# Stepper_2_0.net
KiCad netlist of a schematic drawn in EAGLE
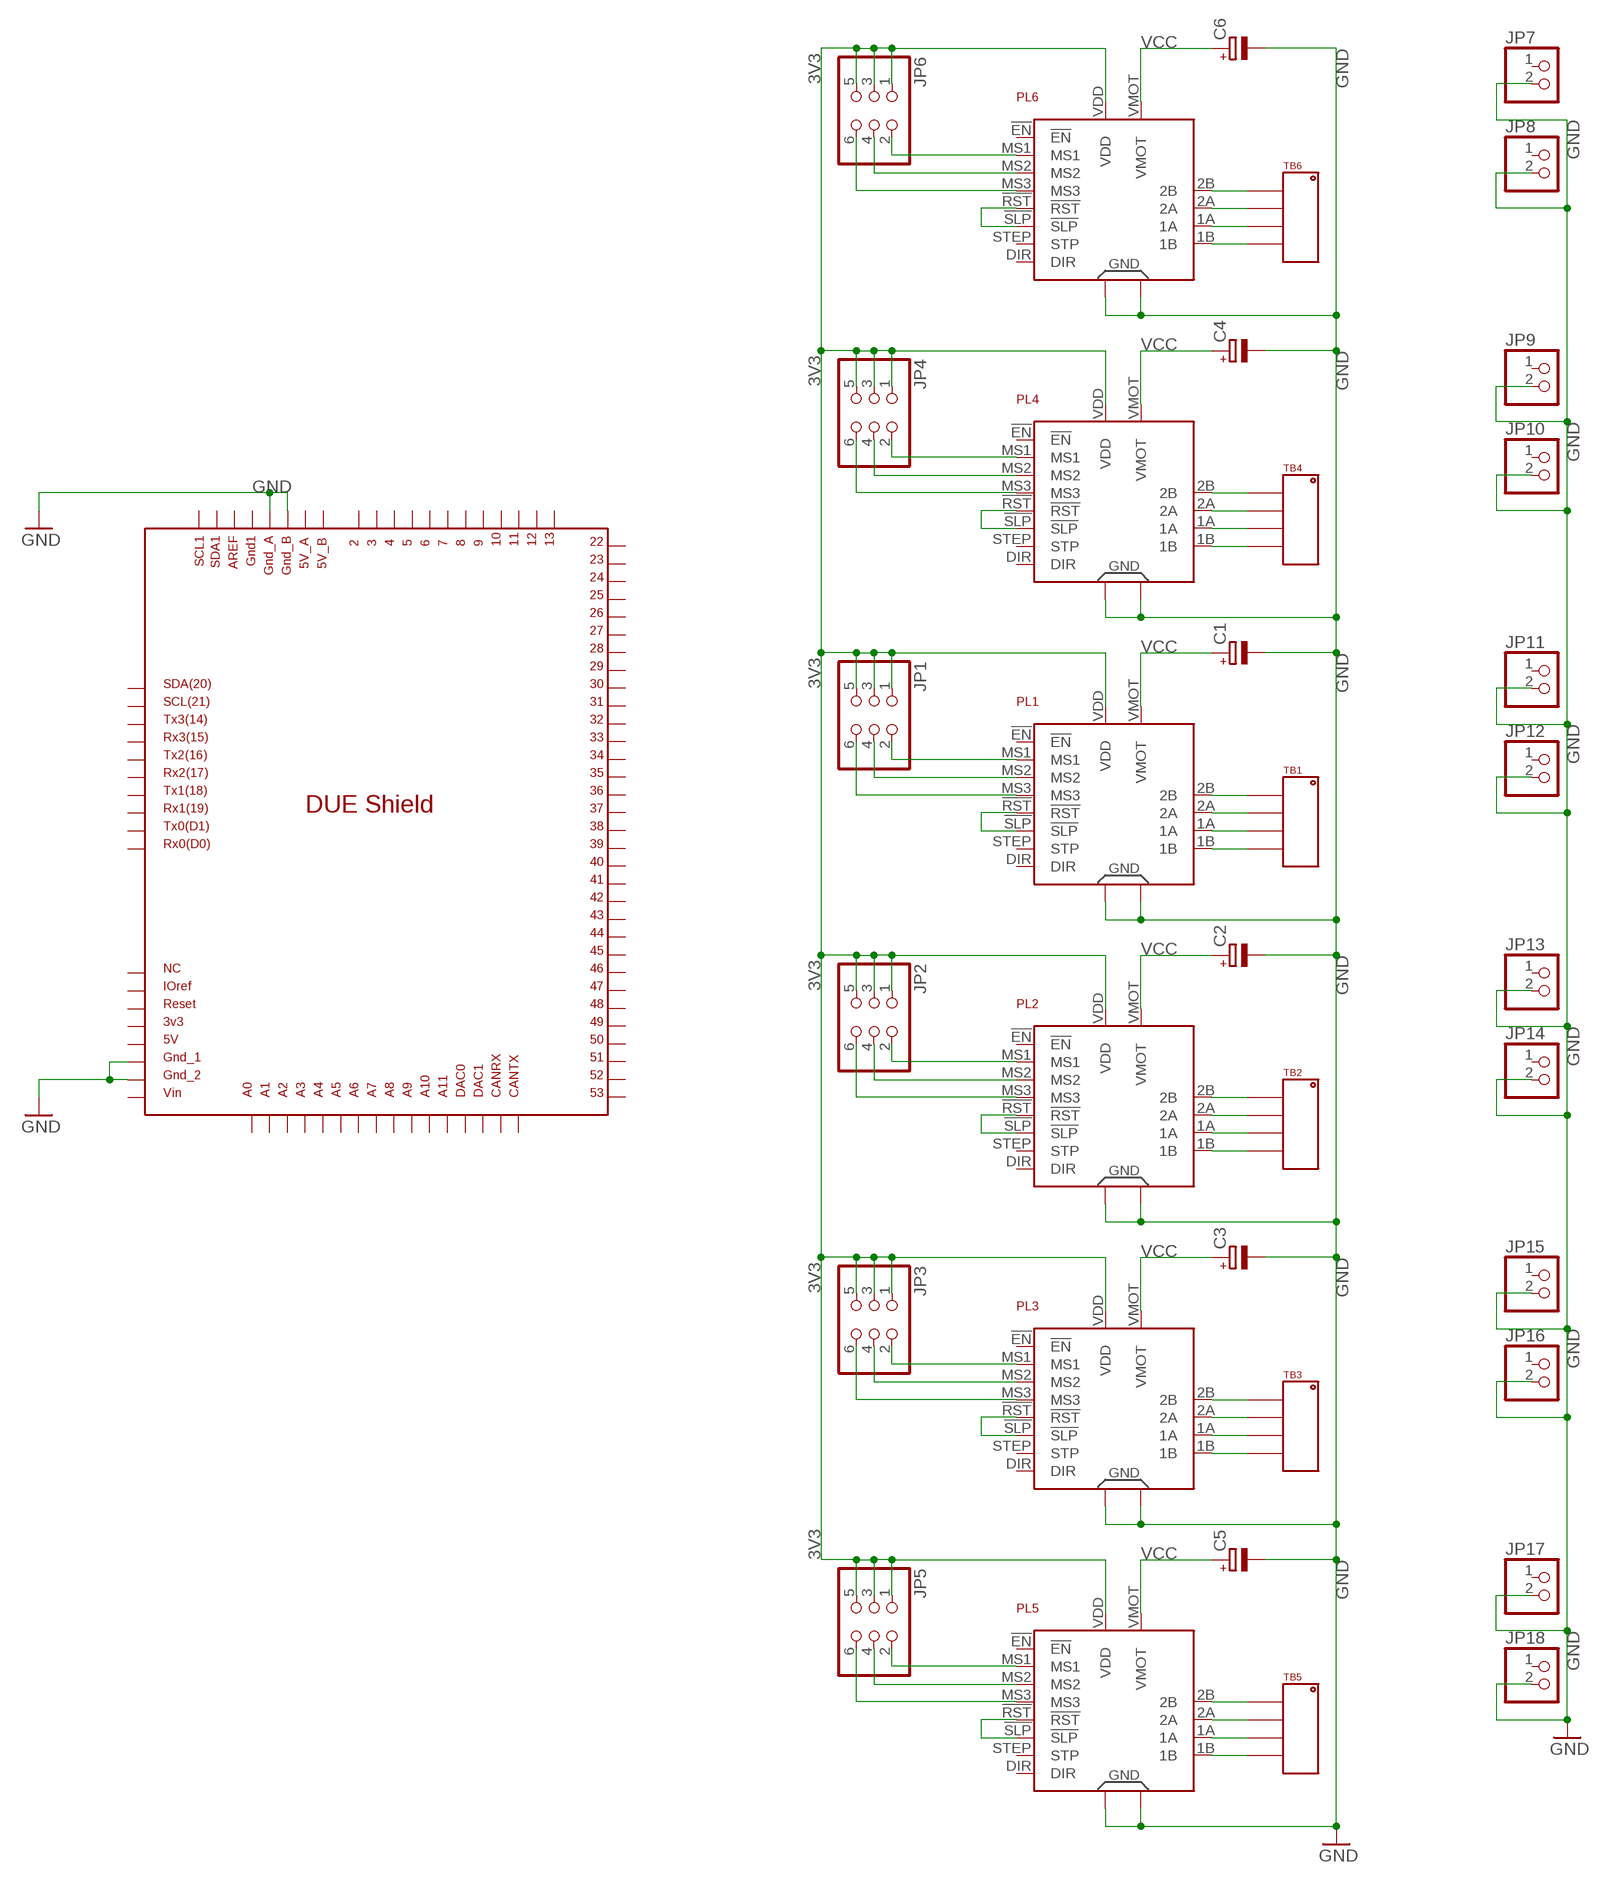
[diagram p0: schematic, sheet 1]

(export (version "E")
  (design (tool "Eeschema 10.0.6"))
  (components
    (comp (ref "C1")
      (value "CPOL-EUETR2")
      (footprint "eagle-import:ETR2")
      (libsource (lib "eagle-import") (part "CPOL-EUETR2"))
    )
    (comp (ref "C2")
      (value "CPOL-EUETR2")
      (footprint "eagle-import:ETR2")
      (libsource (lib "eagle-import") (part "CPOL-EUETR2"))
    )
    (comp (ref "C3")
      (value "CPOL-EUETR2")
      (footprint "eagle-import:ETR2")
      (libsource (lib "eagle-import") (part "CPOL-EUETR2"))
    )
    (comp (ref "C4")
      (value "CPOL-EUETR2")
      (footprint "eagle-import:ETR2")
      (libsource (lib "eagle-import") (part "CPOL-EUETR2"))
    )
    (comp (ref "C5")
      (value "CPOL-EUETR2")
      (footprint "eagle-import:ETR2")
      (libsource (lib "eagle-import") (part "CPOL-EUETR2"))
    )
    (comp (ref "C6")
      (value "CPOL-EUETR2")
      (footprint "eagle-import:ETR2")
      (libsource (lib "eagle-import") (part "CPOL-EUETR2"))
    )
    (comp (ref "JP1")
      (value "PINHD-2X3")
      (footprint "eagle-import:2X03")
      (libsource (lib "eagle-import") (part "PINHD-2X3"))
    )
    (comp (ref "JP2")
      (value "PINHD-2X3")
      (footprint "eagle-import:2X03")
      (libsource (lib "eagle-import") (part "PINHD-2X3"))
    )
    (comp (ref "JP3")
      (value "PINHD-2X3")
      (footprint "eagle-import:2X03")
      (libsource (lib "eagle-import") (part "PINHD-2X3"))
    )
    (comp (ref "JP4")
      (value "PINHD-2X3")
      (footprint "eagle-import:2X03")
      (libsource (lib "eagle-import") (part "PINHD-2X3"))
    )
    (comp (ref "JP5")
      (value "PINHD-2X3")
      (footprint "eagle-import:2X03")
      (libsource (lib "eagle-import") (part "PINHD-2X3"))
    )
    (comp (ref "JP6")
      (value "PINHD-2X3")
      (footprint "eagle-import:2X03")
      (libsource (lib "eagle-import") (part "PINHD-2X3"))
    )
    (comp (ref "JP7")
      (value "PINHD-1X2")
      (footprint "eagle-import:1X02")
      (libsource (lib "eagle-import") (part "PINHD-1X2"))
    )
    (comp (ref "JP8")
      (value "PINHD-1X2")
      (footprint "eagle-import:1X02")
      (libsource (lib "eagle-import") (part "PINHD-1X2"))
    )
    (comp (ref "JP9")
      (value "PINHD-1X2")
      (footprint "eagle-import:1X02")
      (libsource (lib "eagle-import") (part "PINHD-1X2"))
    )
    (comp (ref "JP10")
      (value "PINHD-1X2")
      (footprint "eagle-import:1X02")
      (libsource (lib "eagle-import") (part "PINHD-1X2"))
    )
    (comp (ref "JP11")
      (value "PINHD-1X2")
      (footprint "eagle-import:1X02")
      (libsource (lib "eagle-import") (part "PINHD-1X2"))
    )
    (comp (ref "JP12")
      (value "PINHD-1X2")
      (footprint "eagle-import:1X02")
      (libsource (lib "eagle-import") (part "PINHD-1X2"))
    )
    (comp (ref "JP13")
      (value "PINHD-1X2")
      (footprint "eagle-import:1X02")
      (libsource (lib "eagle-import") (part "PINHD-1X2"))
    )
    (comp (ref "JP14")
      (value "PINHD-1X2")
      (footprint "eagle-import:1X02")
      (libsource (lib "eagle-import") (part "PINHD-1X2"))
    )
    (comp (ref "JP15")
      (value "PINHD-1X2")
      (footprint "eagle-import:1X02")
      (libsource (lib "eagle-import") (part "PINHD-1X2"))
    )
    (comp (ref "JP16")
      (value "PINHD-1X2")
      (footprint "eagle-import:1X02")
      (libsource (lib "eagle-import") (part "PINHD-1X2"))
    )
    (comp (ref "JP17")
      (value "PINHD-1X2")
      (footprint "eagle-import:1X02")
      (libsource (lib "eagle-import") (part "PINHD-1X2"))
    )
    (comp (ref "JP18")
      (value "PINHD-1X2")
      (footprint "eagle-import:1X02")
      (libsource (lib "eagle-import") (part "PINHD-1X2"))
    )
    (comp (ref "PL1")
      (value "A4988X")
      (footprint "eagle-import:MD09X")
      (libsource (lib "eagle-import") (part "A4988X"))
    )
    (comp (ref "PL2")
      (value "A4988X")
      (footprint "eagle-import:MD09X")
      (libsource (lib "eagle-import") (part "A4988X"))
    )
    (comp (ref "PL3")
      (value "A4988X")
      (footprint "eagle-import:MD09X")
      (libsource (lib "eagle-import") (part "A4988X"))
    )
    (comp (ref "PL4")
      (value "A4988X")
      (footprint "eagle-import:MD09X")
      (libsource (lib "eagle-import") (part "A4988X"))
    )
    (comp (ref "PL5")
      (value "A4988X")
      (footprint "eagle-import:MD09X")
      (libsource (lib "eagle-import") (part "A4988X"))
    )
    (comp (ref "PL6")
      (value "A4988X")
      (footprint "eagle-import:MD09X")
      (libsource (lib "eagle-import") (part "A4988X"))
    )
    (comp (ref "TB1")
      (value "TB_HEAD_3.5MM_01X04")
      (footprint "eagle-import:TB_HEAD_3.5MM_01X04")
      (libsource (lib "eagle-import") (part "TB_HEAD_3.5MM_01X04"))
    )
    (comp (ref "TB2")
      (value "TB_HEAD_3.5MM_01X04")
      (footprint "eagle-import:TB_HEAD_3.5MM_01X04")
      (libsource (lib "eagle-import") (part "TB_HEAD_3.5MM_01X04"))
    )
    (comp (ref "TB3")
      (value "TB_HEAD_3.5MM_01X04")
      (footprint "eagle-import:TB_HEAD_3.5MM_01X04")
      (libsource (lib "eagle-import") (part "TB_HEAD_3.5MM_01X04"))
    )
    (comp (ref "TB4")
      (value "TB_HEAD_3.5MM_01X04")
      (footprint "eagle-import:TB_HEAD_3.5MM_01X04")
      (libsource (lib "eagle-import") (part "TB_HEAD_3.5MM_01X04"))
    )
    (comp (ref "TB5")
      (value "TB_HEAD_3.5MM_01X04")
      (footprint "eagle-import:TB_HEAD_3.5MM_01X04")
      (libsource (lib "eagle-import") (part "TB_HEAD_3.5MM_01X04"))
    )
    (comp (ref "TB6")
      (value "TB_HEAD_3.5MM_01X04")
      (footprint "eagle-import:TB_HEAD_3.5MM_01X04")
      (libsource (lib "eagle-import") (part "TB_HEAD_3.5MM_01X04"))
    )
    (comp (ref "U$1")
      (value "DUE(NOSPI)")
      (footprint "eagle-import:DUE(NOSPI)")
      (libsource (lib "eagle-import") (part "DUE(NOSPI)"))
    )
  )
  (nets
    (net (code "1") (name "/3V3") (class "Default")
      (node (ref "JP1") (pin "1") (pinfunction "1_1") (pintype "passive"))
      (node (ref "JP1") (pin "3") (pinfunction "3_3") (pintype "passive"))
      (node (ref "JP1") (pin "5") (pinfunction "5_5") (pintype "passive"))
      (node (ref "JP2") (pin "1") (pinfunction "1_1") (pintype "passive"))
      (node (ref "JP2") (pin "3") (pinfunction "3_3") (pintype "passive"))
      (node (ref "JP2") (pin "5") (pinfunction "5_5") (pintype "passive"))
      (node (ref "JP3") (pin "1") (pinfunction "1_1") (pintype "passive"))
      (node (ref "JP3") (pin "3") (pinfunction "3_3") (pintype "passive"))
      (node (ref "JP3") (pin "5") (pinfunction "5_5") (pintype "passive"))
      (node (ref "JP4") (pin "1") (pinfunction "1_1") (pintype "passive"))
      (node (ref "JP4") (pin "3") (pinfunction "3_3") (pintype "passive"))
      (node (ref "JP4") (pin "5") (pinfunction "5_5") (pintype "passive"))
      (node (ref "JP5") (pin "1") (pinfunction "1_1") (pintype "passive"))
      (node (ref "JP5") (pin "3") (pinfunction "3_3") (pintype "passive"))
      (node (ref "JP5") (pin "5") (pinfunction "5_5") (pintype "passive"))
      (node (ref "JP6") (pin "1") (pinfunction "1_1") (pintype "passive"))
      (node (ref "JP6") (pin "3") (pinfunction "3_3") (pintype "passive"))
      (node (ref "JP6") (pin "5") (pinfunction "5_5") (pintype "passive"))
      (node (ref "PL1") (pin "VDD") (pinfunction "VDD_VDD") (pintype "bidirectional"))
      (node (ref "PL2") (pin "VDD") (pinfunction "VDD_VDD") (pintype "bidirectional"))
      (node (ref "PL3") (pin "VDD") (pinfunction "VDD_VDD") (pintype "bidirectional"))
      (node (ref "PL4") (pin "VDD") (pinfunction "VDD_VDD") (pintype "bidirectional"))
      (node (ref "PL5") (pin "VDD") (pinfunction "VDD_VDD") (pintype "bidirectional"))
      (node (ref "PL6") (pin "VDD") (pinfunction "VDD_VDD") (pintype "bidirectional"))
    )
    (net (code "2") (name "/VCC") (class "Default")
      (node (ref "C1") (pin "+") (pinfunction "+_+") (pintype "passive"))
      (node (ref "C2") (pin "+") (pinfunction "+_+") (pintype "passive"))
      (node (ref "C3") (pin "+") (pinfunction "+_+") (pintype "passive"))
      (node (ref "C4") (pin "+") (pinfunction "+_+") (pintype "passive"))
      (node (ref "C5") (pin "+") (pinfunction "+_+") (pintype "passive"))
      (node (ref "C6") (pin "+") (pinfunction "+_+") (pintype "passive"))
      (node (ref "PL1") (pin "VMOT") (pinfunction "VMOT_VMOT") (pintype "bidirectional"))
      (node (ref "PL2") (pin "VMOT") (pinfunction "VMOT_VMOT") (pintype "bidirectional"))
      (node (ref "PL3") (pin "VMOT") (pinfunction "VMOT_VMOT") (pintype "bidirectional"))
      (node (ref "PL4") (pin "VMOT") (pinfunction "VMOT_VMOT") (pintype "bidirectional"))
      (node (ref "PL5") (pin "VMOT") (pinfunction "VMOT_VMOT") (pintype "bidirectional"))
      (node (ref "PL6") (pin "VMOT") (pinfunction "VMOT_VMOT") (pintype "bidirectional"))
    )
    (net (code "3") (name "GND") (class "Default")
      (node (ref "C1") (pin "-") (pinfunction "-_-") (pintype "passive"))
      (node (ref "C2") (pin "-") (pinfunction "-_-") (pintype "passive"))
      (node (ref "C3") (pin "-") (pinfunction "-_-") (pintype "passive"))
      (node (ref "C4") (pin "-") (pinfunction "-_-") (pintype "passive"))
      (node (ref "C5") (pin "-") (pinfunction "-_-") (pintype "passive"))
      (node (ref "C6") (pin "-") (pinfunction "-_-") (pintype "passive"))
      (node (ref "JP10") (pin "2") (pinfunction "2_2") (pintype "passive"))
      (node (ref "JP11") (pin "2") (pinfunction "2_2") (pintype "passive"))
      (node (ref "JP12") (pin "2") (pinfunction "2_2") (pintype "passive"))
      (node (ref "JP13") (pin "2") (pinfunction "2_2") (pintype "passive"))
      (node (ref "JP14") (pin "2") (pinfunction "2_2") (pintype "passive"))
      (node (ref "JP15") (pin "2") (pinfunction "2_2") (pintype "passive"))
      (node (ref "JP16") (pin "2") (pinfunction "2_2") (pintype "passive"))
      (node (ref "JP17") (pin "2") (pinfunction "2_2") (pintype "passive"))
      (node (ref "JP18") (pin "2") (pinfunction "2_2") (pintype "passive"))
      (node (ref "JP7") (pin "2") (pinfunction "2_2") (pintype "passive"))
      (node (ref "JP8") (pin "2") (pinfunction "2_2") (pintype "passive"))
      (node (ref "JP9") (pin "2") (pinfunction "2_2") (pintype "passive"))
      (node (ref "PL1") (pin "GND1") (pinfunction "GND1_GND1") (pintype "bidirectional"))
      (node (ref "PL1") (pin "GND2") (pinfunction "GND2_GND2") (pintype "bidirectional"))
      (node (ref "PL2") (pin "GND1") (pinfunction "GND1_GND1") (pintype "bidirectional"))
      (node (ref "PL2") (pin "GND2") (pinfunction "GND2_GND2") (pintype "bidirectional"))
      (node (ref "PL3") (pin "GND1") (pinfunction "GND1_GND1") (pintype "bidirectional"))
      (node (ref "PL3") (pin "GND2") (pinfunction "GND2_GND2") (pintype "bidirectional"))
      (node (ref "PL4") (pin "GND1") (pinfunction "GND1_GND1") (pintype "bidirectional"))
      (node (ref "PL4") (pin "GND2") (pinfunction "GND2_GND2") (pintype "bidirectional"))
      (node (ref "PL5") (pin "GND1") (pinfunction "GND1_GND1") (pintype "bidirectional"))
      (node (ref "PL5") (pin "GND2") (pinfunction "GND2_GND2") (pintype "bidirectional"))
      (node (ref "PL6") (pin "GND1") (pinfunction "GND1_GND1") (pintype "bidirectional"))
      (node (ref "PL6") (pin "GND2") (pinfunction "GND2_GND2") (pintype "bidirectional"))
      (node (ref "U$1") (pin "GND_1") (pinfunction "GND_1_GND_1") (pintype "bidirectional"))
      (node (ref "U$1") (pin "GND_2") (pinfunction "GND_2_GND_2") (pintype "bidirectional"))
      (node (ref "U$1") (pin "GND_A") (pinfunction "GND_A_GND_A") (pintype "bidirectional"))
      (node (ref "U$1") (pin "GND_B") (pinfunction "GND_B_GND_B") (pintype "bidirectional"))
    )
    (net (code "4") (name "Net-(JP1-Pad2)") (class "Default")
      (node (ref "JP1") (pin "2") (pinfunction "2_2") (pintype "passive"))
      (node (ref "PL1") (pin "MS1") (pinfunction "MS1_MS1") (pintype "bidirectional"))
    )
    (net (code "5") (name "Net-(JP1-Pad4)") (class "Default")
      (node (ref "JP1") (pin "4") (pinfunction "4_4") (pintype "passive"))
      (node (ref "PL1") (pin "MS2") (pinfunction "MS2_MS2") (pintype "bidirectional"))
    )
    (net (code "6") (name "Net-(JP1-Pad6)") (class "Default")
      (node (ref "JP1") (pin "6") (pinfunction "6_6") (pintype "passive"))
      (node (ref "PL1") (pin "MS3") (pinfunction "MS3_MS3") (pintype "bidirectional"))
    )
    (net (code "7") (name "Net-(JP2-Pad2)") (class "Default")
      (node (ref "JP2") (pin "2") (pinfunction "2_2") (pintype "passive"))
      (node (ref "PL2") (pin "MS1") (pinfunction "MS1_MS1") (pintype "bidirectional"))
    )
    (net (code "8") (name "Net-(JP2-Pad4)") (class "Default")
      (node (ref "JP2") (pin "4") (pinfunction "4_4") (pintype "passive"))
      (node (ref "PL2") (pin "MS2") (pinfunction "MS2_MS2") (pintype "bidirectional"))
    )
    (net (code "9") (name "Net-(JP2-Pad6)") (class "Default")
      (node (ref "JP2") (pin "6") (pinfunction "6_6") (pintype "passive"))
      (node (ref "PL2") (pin "MS3") (pinfunction "MS3_MS3") (pintype "bidirectional"))
    )
    (net (code "10") (name "Net-(JP3-Pad2)") (class "Default")
      (node (ref "JP3") (pin "2") (pinfunction "2_2") (pintype "passive"))
      (node (ref "PL3") (pin "MS1") (pinfunction "MS1_MS1") (pintype "bidirectional"))
    )
    (net (code "11") (name "Net-(JP3-Pad4)") (class "Default")
      (node (ref "JP3") (pin "4") (pinfunction "4_4") (pintype "passive"))
      (node (ref "PL3") (pin "MS2") (pinfunction "MS2_MS2") (pintype "bidirectional"))
    )
    (net (code "12") (name "Net-(JP3-Pad6)") (class "Default")
      (node (ref "JP3") (pin "6") (pinfunction "6_6") (pintype "passive"))
      (node (ref "PL3") (pin "MS3") (pinfunction "MS3_MS3") (pintype "bidirectional"))
    )
    (net (code "13") (name "Net-(JP4-Pad2)") (class "Default")
      (node (ref "JP4") (pin "2") (pinfunction "2_2") (pintype "passive"))
      (node (ref "PL4") (pin "MS1") (pinfunction "MS1_MS1") (pintype "bidirectional"))
    )
    (net (code "14") (name "Net-(JP4-Pad4)") (class "Default")
      (node (ref "JP4") (pin "4") (pinfunction "4_4") (pintype "passive"))
      (node (ref "PL4") (pin "MS2") (pinfunction "MS2_MS2") (pintype "bidirectional"))
    )
    (net (code "15") (name "Net-(JP4-Pad6)") (class "Default")
      (node (ref "JP4") (pin "6") (pinfunction "6_6") (pintype "passive"))
      (node (ref "PL4") (pin "MS3") (pinfunction "MS3_MS3") (pintype "bidirectional"))
    )
    (net (code "16") (name "Net-(JP5-Pad2)") (class "Default")
      (node (ref "JP5") (pin "2") (pinfunction "2_2") (pintype "passive"))
      (node (ref "PL5") (pin "MS1") (pinfunction "MS1_MS1") (pintype "bidirectional"))
    )
    (net (code "17") (name "Net-(JP5-Pad4)") (class "Default")
      (node (ref "JP5") (pin "4") (pinfunction "4_4") (pintype "passive"))
      (node (ref "PL5") (pin "MS2") (pinfunction "MS2_MS2") (pintype "bidirectional"))
    )
    (net (code "18") (name "Net-(JP5-Pad6)") (class "Default")
      (node (ref "JP5") (pin "6") (pinfunction "6_6") (pintype "passive"))
      (node (ref "PL5") (pin "MS3") (pinfunction "MS3_MS3") (pintype "bidirectional"))
    )
    (net (code "19") (name "Net-(JP6-Pad2)") (class "Default")
      (node (ref "JP6") (pin "2") (pinfunction "2_2") (pintype "passive"))
      (node (ref "PL6") (pin "MS1") (pinfunction "MS1_MS1") (pintype "bidirectional"))
    )
    (net (code "20") (name "Net-(JP6-Pad4)") (class "Default")
      (node (ref "JP6") (pin "4") (pinfunction "4_4") (pintype "passive"))
      (node (ref "PL6") (pin "MS2") (pinfunction "MS2_MS2") (pintype "bidirectional"))
    )
    (net (code "21") (name "Net-(JP6-Pad6)") (class "Default")
      (node (ref "JP6") (pin "6") (pinfunction "6_6") (pintype "passive"))
      (node (ref "PL6") (pin "MS3") (pinfunction "MS3_MS3") (pintype "bidirectional"))
    )
    (net (code "22") (name "Net-(PL1-Pad1A)") (class "Default")
      (node (ref "PL1") (pin "1A") (pinfunction "1A_1A") (pintype "bidirectional"))
      (node (ref "TB1") (pin "P$3") (pinfunction "P$3_P$3") (pintype "bidirectional"))
    )
    (net (code "23") (name "Net-(PL1-Pad1B)") (class "Default")
      (node (ref "PL1") (pin "1B") (pinfunction "1B_1B") (pintype "bidirectional"))
      (node (ref "TB1") (pin "P$4") (pinfunction "P$4_P$4") (pintype "bidirectional"))
    )
    (net (code "24") (name "Net-(PL1-Pad2A)") (class "Default")
      (node (ref "PL1") (pin "2A") (pinfunction "2A_2A") (pintype "bidirectional"))
      (node (ref "TB1") (pin "P$2") (pinfunction "P$2_P$2") (pintype "bidirectional"))
    )
    (net (code "25") (name "Net-(PL1-Pad2B)") (class "Default")
      (node (ref "PL1") (pin "2B") (pinfunction "2B_2B") (pintype "bidirectional"))
      (node (ref "TB1") (pin "P$1") (pinfunction "P$1_P$1") (pintype "bidirectional"))
    )
    (net (code "26") (name "Net-(PL1-~{RST})") (class "Default")
      (node (ref "PL1") (pin "!RST") (pinfunction "~{RST}_!RST") (pintype "bidirectional"))
      (node (ref "PL1") (pin "!SLP") (pinfunction "~{SLP}_!SLP") (pintype "bidirectional"))
    )
    (net (code "27") (name "Net-(PL2-Pad1A)") (class "Default")
      (node (ref "PL2") (pin "1A") (pinfunction "1A_1A") (pintype "bidirectional"))
      (node (ref "TB2") (pin "P$3") (pinfunction "P$3_P$3") (pintype "bidirectional"))
    )
    (net (code "28") (name "Net-(PL2-Pad1B)") (class "Default")
      (node (ref "PL2") (pin "1B") (pinfunction "1B_1B") (pintype "bidirectional"))
      (node (ref "TB2") (pin "P$4") (pinfunction "P$4_P$4") (pintype "bidirectional"))
    )
    (net (code "29") (name "Net-(PL2-Pad2A)") (class "Default")
      (node (ref "PL2") (pin "2A") (pinfunction "2A_2A") (pintype "bidirectional"))
      (node (ref "TB2") (pin "P$2") (pinfunction "P$2_P$2") (pintype "bidirectional"))
    )
    (net (code "30") (name "Net-(PL2-Pad2B)") (class "Default")
      (node (ref "PL2") (pin "2B") (pinfunction "2B_2B") (pintype "bidirectional"))
      (node (ref "TB2") (pin "P$1") (pinfunction "P$1_P$1") (pintype "bidirectional"))
    )
    (net (code "31") (name "Net-(PL2-~{RST})") (class "Default")
      (node (ref "PL2") (pin "!RST") (pinfunction "~{RST}_!RST") (pintype "bidirectional"))
      (node (ref "PL2") (pin "!SLP") (pinfunction "~{SLP}_!SLP") (pintype "bidirectional"))
    )
    (net (code "32") (name "Net-(PL3-Pad1A)") (class "Default")
      (node (ref "PL3") (pin "1A") (pinfunction "1A_1A") (pintype "bidirectional"))
      (node (ref "TB3") (pin "P$3") (pinfunction "P$3_P$3") (pintype "bidirectional"))
    )
    (net (code "33") (name "Net-(PL3-Pad1B)") (class "Default")
      (node (ref "PL3") (pin "1B") (pinfunction "1B_1B") (pintype "bidirectional"))
      (node (ref "TB3") (pin "P$4") (pinfunction "P$4_P$4") (pintype "bidirectional"))
    )
    (net (code "34") (name "Net-(PL3-Pad2A)") (class "Default")
      (node (ref "PL3") (pin "2A") (pinfunction "2A_2A") (pintype "bidirectional"))
      (node (ref "TB3") (pin "P$2") (pinfunction "P$2_P$2") (pintype "bidirectional"))
    )
    (net (code "35") (name "Net-(PL3-Pad2B)") (class "Default")
      (node (ref "PL3") (pin "2B") (pinfunction "2B_2B") (pintype "bidirectional"))
      (node (ref "TB3") (pin "P$1") (pinfunction "P$1_P$1") (pintype "bidirectional"))
    )
    (net (code "36") (name "Net-(PL3-~{RST})") (class "Default")
      (node (ref "PL3") (pin "!RST") (pinfunction "~{RST}_!RST") (pintype "bidirectional"))
      (node (ref "PL3") (pin "!SLP") (pinfunction "~{SLP}_!SLP") (pintype "bidirectional"))
    )
    (net (code "37") (name "Net-(PL4-Pad1A)") (class "Default")
      (node (ref "PL4") (pin "1A") (pinfunction "1A_1A") (pintype "bidirectional"))
      (node (ref "TB4") (pin "P$3") (pinfunction "P$3_P$3") (pintype "bidirectional"))
    )
    (net (code "38") (name "Net-(PL4-Pad1B)") (class "Default")
      (node (ref "PL4") (pin "1B") (pinfunction "1B_1B") (pintype "bidirectional"))
      (node (ref "TB4") (pin "P$4") (pinfunction "P$4_P$4") (pintype "bidirectional"))
    )
    (net (code "39") (name "Net-(PL4-Pad2A)") (class "Default")
      (node (ref "PL4") (pin "2A") (pinfunction "2A_2A") (pintype "bidirectional"))
      (node (ref "TB4") (pin "P$2") (pinfunction "P$2_P$2") (pintype "bidirectional"))
    )
    (net (code "40") (name "Net-(PL4-Pad2B)") (class "Default")
      (node (ref "PL4") (pin "2B") (pinfunction "2B_2B") (pintype "bidirectional"))
      (node (ref "TB4") (pin "P$1") (pinfunction "P$1_P$1") (pintype "bidirectional"))
    )
    (net (code "41") (name "Net-(PL4-~{RST})") (class "Default")
      (node (ref "PL4") (pin "!RST") (pinfunction "~{RST}_!RST") (pintype "bidirectional"))
      (node (ref "PL4") (pin "!SLP") (pinfunction "~{SLP}_!SLP") (pintype "bidirectional"))
    )
    (net (code "42") (name "Net-(PL5-Pad1A)") (class "Default")
      (node (ref "PL5") (pin "1A") (pinfunction "1A_1A") (pintype "bidirectional"))
      (node (ref "TB5") (pin "P$3") (pinfunction "P$3_P$3") (pintype "bidirectional"))
    )
    (net (code "43") (name "Net-(PL5-Pad1B)") (class "Default")
      (node (ref "PL5") (pin "1B") (pinfunction "1B_1B") (pintype "bidirectional"))
      (node (ref "TB5") (pin "P$4") (pinfunction "P$4_P$4") (pintype "bidirectional"))
    )
    (net (code "44") (name "Net-(PL5-Pad2A)") (class "Default")
      (node (ref "PL5") (pin "2A") (pinfunction "2A_2A") (pintype "bidirectional"))
      (node (ref "TB5") (pin "P$2") (pinfunction "P$2_P$2") (pintype "bidirectional"))
    )
    (net (code "45") (name "Net-(PL5-Pad2B)") (class "Default")
      (node (ref "PL5") (pin "2B") (pinfunction "2B_2B") (pintype "bidirectional"))
      (node (ref "TB5") (pin "P$1") (pinfunction "P$1_P$1") (pintype "bidirectional"))
    )
    (net (code "46") (name "Net-(PL5-~{RST})") (class "Default")
      (node (ref "PL5") (pin "!RST") (pinfunction "~{RST}_!RST") (pintype "bidirectional"))
      (node (ref "PL5") (pin "!SLP") (pinfunction "~{SLP}_!SLP") (pintype "bidirectional"))
    )
    (net (code "47") (name "Net-(PL6-Pad1A)") (class "Default")
      (node (ref "PL6") (pin "1A") (pinfunction "1A_1A") (pintype "bidirectional"))
      (node (ref "TB6") (pin "P$3") (pinfunction "P$3_P$3") (pintype "bidirectional"))
    )
    (net (code "48") (name "Net-(PL6-Pad1B)") (class "Default")
      (node (ref "PL6") (pin "1B") (pinfunction "1B_1B") (pintype "bidirectional"))
      (node (ref "TB6") (pin "P$4") (pinfunction "P$4_P$4") (pintype "bidirectional"))
    )
    (net (code "49") (name "Net-(PL6-Pad2A)") (class "Default")
      (node (ref "PL6") (pin "2A") (pinfunction "2A_2A") (pintype "bidirectional"))
      (node (ref "TB6") (pin "P$2") (pinfunction "P$2_P$2") (pintype "bidirectional"))
    )
    (net (code "50") (name "Net-(PL6-Pad2B)") (class "Default")
      (node (ref "PL6") (pin "2B") (pinfunction "2B_2B") (pintype "bidirectional"))
      (node (ref "TB6") (pin "P$1") (pinfunction "P$1_P$1") (pintype "bidirectional"))
    )
    (net (code "51") (name "Net-(PL6-~{RST})") (class "Default")
      (node (ref "PL6") (pin "!RST") (pinfunction "~{RST}_!RST") (pintype "bidirectional"))
      (node (ref "PL6") (pin "!SLP") (pinfunction "~{SLP}_!SLP") (pintype "bidirectional"))
    )
    (net (code "52") (name "unconnected-(JP7-Pad1)") (class "Default")
      (node (ref "JP7") (pin "1") (pinfunction "1_1") (pintype "passive"))
    )
    (net (code "53") (name "unconnected-(JP8-Pad1)") (class "Default")
      (node (ref "JP8") (pin "1") (pinfunction "1_1") (pintype "passive"))
    )
    (net (code "54") (name "unconnected-(JP9-Pad1)") (class "Default")
      (node (ref "JP9") (pin "1") (pinfunction "1_1") (pintype "passive"))
    )
    (net (code "55") (name "unconnected-(JP10-Pad1)") (class "Default")
      (node (ref "JP10") (pin "1") (pinfunction "1_1") (pintype "passive"))
    )
    (net (code "56") (name "unconnected-(JP11-Pad1)") (class "Default")
      (node (ref "JP11") (pin "1") (pinfunction "1_1") (pintype "passive"))
    )
    (net (code "57") (name "unconnected-(JP12-Pad1)") (class "Default")
      (node (ref "JP12") (pin "1") (pinfunction "1_1") (pintype "passive"))
    )
    (net (code "58") (name "unconnected-(JP13-Pad1)") (class "Default")
      (node (ref "JP13") (pin "1") (pinfunction "1_1") (pintype "passive"))
    )
    (net (code "59") (name "unconnected-(JP14-Pad1)") (class "Default")
      (node (ref "JP14") (pin "1") (pinfunction "1_1") (pintype "passive"))
    )
    (net (code "60") (name "unconnected-(JP15-Pad1)") (class "Default")
      (node (ref "JP15") (pin "1") (pinfunction "1_1") (pintype "passive"))
    )
    (net (code "61") (name "unconnected-(JP16-Pad1)") (class "Default")
      (node (ref "JP16") (pin "1") (pinfunction "1_1") (pintype "passive"))
    )
    (net (code "62") (name "unconnected-(JP17-Pad1)") (class "Default")
      (node (ref "JP17") (pin "1") (pinfunction "1_1") (pintype "passive"))
    )
    (net (code "63") (name "unconnected-(JP18-Pad1)") (class "Default")
      (node (ref "JP18") (pin "1") (pinfunction "1_1") (pintype "passive"))
    )
    (net (code "64") (name "unconnected-(PL1-PadDIR)") (class "Default")
      (node (ref "PL1") (pin "DIR") (pinfunction "DIR_DIR") (pintype "bidirectional"))
    )
    (net (code "65") (name "unconnected-(PL1-STP-PadSTEP)") (class "Default")
      (node (ref "PL1") (pin "STEP") (pinfunction "STP_STEP") (pintype "bidirectional"))
    )
    (net (code "66") (name "unconnected-(PL1-~{EN}-Pad!EN)") (class "Default")
      (node (ref "PL1") (pin "!EN") (pinfunction "~{EN}_!EN") (pintype "bidirectional"))
    )
    (net (code "67") (name "unconnected-(PL2-PadDIR)") (class "Default")
      (node (ref "PL2") (pin "DIR") (pinfunction "DIR_DIR") (pintype "bidirectional"))
    )
    (net (code "68") (name "unconnected-(PL2-STP-PadSTEP)") (class "Default")
      (node (ref "PL2") (pin "STEP") (pinfunction "STP_STEP") (pintype "bidirectional"))
    )
    (net (code "69") (name "unconnected-(PL2-~{EN}-Pad!EN)") (class "Default")
      (node (ref "PL2") (pin "!EN") (pinfunction "~{EN}_!EN") (pintype "bidirectional"))
    )
    (net (code "70") (name "unconnected-(PL3-PadDIR)") (class "Default")
      (node (ref "PL3") (pin "DIR") (pinfunction "DIR_DIR") (pintype "bidirectional"))
    )
    (net (code "71") (name "unconnected-(PL3-STP-PadSTEP)") (class "Default")
      (node (ref "PL3") (pin "STEP") (pinfunction "STP_STEP") (pintype "bidirectional"))
    )
    (net (code "72") (name "unconnected-(PL3-~{EN}-Pad!EN)") (class "Default")
      (node (ref "PL3") (pin "!EN") (pinfunction "~{EN}_!EN") (pintype "bidirectional"))
    )
    (net (code "73") (name "unconnected-(PL4-PadDIR)") (class "Default")
      (node (ref "PL4") (pin "DIR") (pinfunction "DIR_DIR") (pintype "bidirectional"))
    )
    (net (code "74") (name "unconnected-(PL4-STP-PadSTEP)") (class "Default")
      (node (ref "PL4") (pin "STEP") (pinfunction "STP_STEP") (pintype "bidirectional"))
    )
    (net (code "75") (name "unconnected-(PL4-~{EN}-Pad!EN)") (class "Default")
      (node (ref "PL4") (pin "!EN") (pinfunction "~{EN}_!EN") (pintype "bidirectional"))
    )
    (net (code "76") (name "unconnected-(PL5-PadDIR)") (class "Default")
      (node (ref "PL5") (pin "DIR") (pinfunction "DIR_DIR") (pintype "bidirectional"))
    )
    (net (code "77") (name "unconnected-(PL5-STP-PadSTEP)") (class "Default")
      (node (ref "PL5") (pin "STEP") (pinfunction "STP_STEP") (pintype "bidirectional"))
    )
    (net (code "78") (name "unconnected-(PL5-~{EN}-Pad!EN)") (class "Default")
      (node (ref "PL5") (pin "!EN") (pinfunction "~{EN}_!EN") (pintype "bidirectional"))
    )
    (net (code "79") (name "unconnected-(PL6-PadDIR)") (class "Default")
      (node (ref "PL6") (pin "DIR") (pinfunction "DIR_DIR") (pintype "bidirectional"))
    )
    (net (code "80") (name "unconnected-(PL6-STP-PadSTEP)") (class "Default")
      (node (ref "PL6") (pin "STEP") (pinfunction "STP_STEP") (pintype "bidirectional"))
    )
    (net (code "81") (name "unconnected-(PL6-~{EN}-Pad!EN)") (class "Default")
      (node (ref "PL6") (pin "!EN") (pinfunction "~{EN}_!EN") (pintype "bidirectional"))
    )
    (net (code "82") (name "unconnected-(U$1-Pad2)") (class "Default")
      (node (ref "U$1") (pin "2") (pinfunction "2_2") (pintype "bidirectional"))
    )
    (net (code "83") (name "unconnected-(U$1-Pad3)") (class "Default")
      (node (ref "U$1") (pin "3") (pinfunction "3_3") (pintype "bidirectional"))
    )
    (net (code "84") (name "unconnected-(U$1-Pad3V3)") (class "Default")
      (node (ref "U$1") (pin "3V3") (pinfunction "3V3_3V3") (pintype "bidirectional"))
    )
    (net (code "85") (name "unconnected-(U$1-Pad4)") (class "Default")
      (node (ref "U$1") (pin "4") (pinfunction "4_4") (pintype "bidirectional"))
    )
    (net (code "86") (name "unconnected-(U$1-Pad5)") (class "Default")
      (node (ref "U$1") (pin "5") (pinfunction "5_5") (pintype "bidirectional"))
    )
    (net (code "87") (name "unconnected-(U$1-Pad5V)") (class "Default")
      (node (ref "U$1") (pin "5V") (pinfunction "5V_5V") (pintype "bidirectional"))
    )
    (net (code "88") (name "unconnected-(U$1-Pad5V_A)") (class "Default")
      (node (ref "U$1") (pin "5V_A") (pinfunction "5V_A_5V_A") (pintype "bidirectional"))
    )
    (net (code "89") (name "unconnected-(U$1-Pad5V_B)") (class "Default")
      (node (ref "U$1") (pin "5V_B") (pinfunction "5V_B_5V_B") (pintype "bidirectional"))
    )
    (net (code "90") (name "unconnected-(U$1-Pad6)") (class "Default")
      (node (ref "U$1") (pin "6") (pinfunction "6_6") (pintype "bidirectional"))
    )
    (net (code "91") (name "unconnected-(U$1-Pad7)") (class "Default")
      (node (ref "U$1") (pin "7") (pinfunction "7_7") (pintype "bidirectional"))
    )
    (net (code "92") (name "unconnected-(U$1-Pad8)") (class "Default")
      (node (ref "U$1") (pin "8") (pinfunction "8_8") (pintype "bidirectional"))
    )
    (net (code "93") (name "unconnected-(U$1-Pad9)") (class "Default")
      (node (ref "U$1") (pin "9") (pinfunction "9_9") (pintype "bidirectional"))
    )
    (net (code "94") (name "unconnected-(U$1-Pad10)") (class "Default")
      (node (ref "U$1") (pin "10") (pinfunction "10_10") (pintype "bidirectional"))
    )
    (net (code "95") (name "unconnected-(U$1-Pad11)") (class "Default")
      (node (ref "U$1") (pin "11") (pinfunction "11_11") (pintype "bidirectional"))
    )
    (net (code "96") (name "unconnected-(U$1-Pad12)") (class "Default")
      (node (ref "U$1") (pin "12") (pinfunction "12_12") (pintype "bidirectional"))
    )
    (net (code "97") (name "unconnected-(U$1-Pad13)") (class "Default")
      (node (ref "U$1") (pin "13") (pinfunction "13_13") (pintype "bidirectional"))
    )
    (net (code "98") (name "unconnected-(U$1-Pad22)") (class "Default")
      (node (ref "U$1") (pin "22") (pinfunction "22_22") (pintype "bidirectional"))
    )
    (net (code "99") (name "unconnected-(U$1-Pad23)") (class "Default")
      (node (ref "U$1") (pin "23") (pinfunction "23_23") (pintype "bidirectional"))
    )
    (net (code "100") (name "unconnected-(U$1-Pad24)") (class "Default")
      (node (ref "U$1") (pin "24") (pinfunction "24_24") (pintype "bidirectional"))
    )
    (net (code "101") (name "unconnected-(U$1-Pad25)") (class "Default")
      (node (ref "U$1") (pin "25") (pinfunction "25_25") (pintype "bidirectional"))
    )
    (net (code "102") (name "unconnected-(U$1-Pad26)") (class "Default")
      (node (ref "U$1") (pin "26") (pinfunction "26_26") (pintype "bidirectional"))
    )
    (net (code "103") (name "unconnected-(U$1-Pad27)") (class "Default")
      (node (ref "U$1") (pin "27") (pinfunction "27_27") (pintype "bidirectional"))
    )
    (net (code "104") (name "unconnected-(U$1-Pad28)") (class "Default")
      (node (ref "U$1") (pin "28") (pinfunction "28_28") (pintype "bidirectional"))
    )
    (net (code "105") (name "unconnected-(U$1-Pad29)") (class "Default")
      (node (ref "U$1") (pin "29") (pinfunction "29_29") (pintype "bidirectional"))
    )
    (net (code "106") (name "unconnected-(U$1-Pad30)") (class "Default")
      (node (ref "U$1") (pin "30") (pinfunction "30_30") (pintype "bidirectional"))
    )
    (net (code "107") (name "unconnected-(U$1-Pad31)") (class "Default")
      (node (ref "U$1") (pin "31") (pinfunction "31_31") (pintype "bidirectional"))
    )
    (net (code "108") (name "unconnected-(U$1-Pad32)") (class "Default")
      (node (ref "U$1") (pin "32") (pinfunction "32_32") (pintype "bidirectional"))
    )
    (net (code "109") (name "unconnected-(U$1-Pad33)") (class "Default")
      (node (ref "U$1") (pin "33") (pinfunction "33_33") (pintype "bidirectional"))
    )
    (net (code "110") (name "unconnected-(U$1-Pad34)") (class "Default")
      (node (ref "U$1") (pin "34") (pinfunction "34_34") (pintype "bidirectional"))
    )
    (net (code "111") (name "unconnected-(U$1-Pad35)") (class "Default")
      (node (ref "U$1") (pin "35") (pinfunction "35_35") (pintype "bidirectional"))
    )
    (net (code "112") (name "unconnected-(U$1-Pad36)") (class "Default")
      (node (ref "U$1") (pin "36") (pinfunction "36_36") (pintype "bidirectional"))
    )
    (net (code "113") (name "unconnected-(U$1-Pad37)") (class "Default")
      (node (ref "U$1") (pin "37") (pinfunction "37_37") (pintype "bidirectional"))
    )
    (net (code "114") (name "unconnected-(U$1-Pad38)") (class "Default")
      (node (ref "U$1") (pin "38") (pinfunction "38_38") (pintype "bidirectional"))
    )
    (net (code "115") (name "unconnected-(U$1-Pad39)") (class "Default")
      (node (ref "U$1") (pin "39") (pinfunction "39_39") (pintype "bidirectional"))
    )
    (net (code "116") (name "unconnected-(U$1-Pad40)") (class "Default")
      (node (ref "U$1") (pin "40") (pinfunction "40_40") (pintype "bidirectional"))
    )
    (net (code "117") (name "unconnected-(U$1-Pad41)") (class "Default")
      (node (ref "U$1") (pin "41") (pinfunction "41_41") (pintype "bidirectional"))
    )
    (net (code "118") (name "unconnected-(U$1-Pad42)") (class "Default")
      (node (ref "U$1") (pin "42") (pinfunction "42_42") (pintype "bidirectional"))
    )
    (net (code "119") (name "unconnected-(U$1-Pad43)") (class "Default")
      (node (ref "U$1") (pin "43") (pinfunction "43_43") (pintype "bidirectional"))
    )
    (net (code "120") (name "unconnected-(U$1-Pad44)") (class "Default")
      (node (ref "U$1") (pin "44") (pinfunction "44_44") (pintype "bidirectional"))
    )
    (net (code "121") (name "unconnected-(U$1-Pad45)") (class "Default")
      (node (ref "U$1") (pin "45") (pinfunction "45_45") (pintype "bidirectional"))
    )
    (net (code "122") (name "unconnected-(U$1-Pad46)") (class "Default")
      (node (ref "U$1") (pin "46") (pinfunction "46_46") (pintype "bidirectional"))
    )
    (net (code "123") (name "unconnected-(U$1-Pad47)") (class "Default")
      (node (ref "U$1") (pin "47") (pinfunction "47_47") (pintype "bidirectional"))
    )
    (net (code "124") (name "unconnected-(U$1-Pad48)") (class "Default")
      (node (ref "U$1") (pin "48") (pinfunction "48_48") (pintype "bidirectional"))
    )
    (net (code "125") (name "unconnected-(U$1-Pad49)") (class "Default")
      (node (ref "U$1") (pin "49") (pinfunction "49_49") (pintype "bidirectional"))
    )
    (net (code "126") (name "unconnected-(U$1-Pad50)") (class "Default")
      (node (ref "U$1") (pin "50") (pinfunction "50_50") (pintype "bidirectional"))
    )
    (net (code "127") (name "unconnected-(U$1-Pad51)") (class "Default")
      (node (ref "U$1") (pin "51") (pinfunction "51_51") (pintype "bidirectional"))
    )
    (net (code "128") (name "unconnected-(U$1-Pad52)") (class "Default")
      (node (ref "U$1") (pin "52") (pinfunction "52_52") (pintype "bidirectional"))
    )
    (net (code "129") (name "unconnected-(U$1-Pad53)") (class "Default")
      (node (ref "U$1") (pin "53") (pinfunction "53_53") (pintype "bidirectional"))
    )
    (net (code "130") (name "unconnected-(U$1-PadA0)") (class "Default")
      (node (ref "U$1") (pin "A0") (pinfunction "A0_A0") (pintype "bidirectional"))
    )
    (net (code "131") (name "unconnected-(U$1-PadA1)") (class "Default")
      (node (ref "U$1") (pin "A1") (pinfunction "A1_A1") (pintype "bidirectional"))
    )
    (net (code "132") (name "unconnected-(U$1-PadA2)") (class "Default")
      (node (ref "U$1") (pin "A2") (pinfunction "A2_A2") (pintype "bidirectional"))
    )
    (net (code "133") (name "unconnected-(U$1-PadA3)") (class "Default")
      (node (ref "U$1") (pin "A3") (pinfunction "A3_A3") (pintype "bidirectional"))
    )
    (net (code "134") (name "unconnected-(U$1-PadA4)") (class "Default")
      (node (ref "U$1") (pin "A4") (pinfunction "A4_A4") (pintype "bidirectional"))
    )
    (net (code "135") (name "unconnected-(U$1-PadA5)") (class "Default")
      (node (ref "U$1") (pin "A5") (pinfunction "A5_A5") (pintype "bidirectional"))
    )
    (net (code "136") (name "unconnected-(U$1-PadA6)") (class "Default")
      (node (ref "U$1") (pin "A6") (pinfunction "A6_A6") (pintype "bidirectional"))
    )
    (net (code "137") (name "unconnected-(U$1-PadA7)") (class "Default")
      (node (ref "U$1") (pin "A7") (pinfunction "A7_A7") (pintype "bidirectional"))
    )
    (net (code "138") (name "unconnected-(U$1-PadA8)") (class "Default")
      (node (ref "U$1") (pin "A8") (pinfunction "A8_A8") (pintype "bidirectional"))
    )
    (net (code "139") (name "unconnected-(U$1-PadA9)") (class "Default")
      (node (ref "U$1") (pin "A9") (pinfunction "A9_A9") (pintype "bidirectional"))
    )
    (net (code "140") (name "unconnected-(U$1-PadA10)") (class "Default")
      (node (ref "U$1") (pin "A10") (pinfunction "A10_A10") (pintype "bidirectional"))
    )
    (net (code "141") (name "unconnected-(U$1-PadA11)") (class "Default")
      (node (ref "U$1") (pin "A11") (pinfunction "A11_A11") (pintype "bidirectional"))
    )
    (net (code "142") (name "unconnected-(U$1-PadAREF)") (class "Default")
      (node (ref "U$1") (pin "AREF") (pinfunction "AREF_AREF") (pintype "bidirectional"))
    )
    (net (code "143") (name "unconnected-(U$1-PadCANRX)") (class "Default")
      (node (ref "U$1") (pin "CANRX") (pinfunction "CANRX_CANRX") (pintype "bidirectional"))
    )
    (net (code "144") (name "unconnected-(U$1-PadCANTX)") (class "Default")
      (node (ref "U$1") (pin "CANTX") (pinfunction "CANTX_CANTX") (pintype "bidirectional"))
    )
    (net (code "145") (name "unconnected-(U$1-PadDAC0)") (class "Default")
      (node (ref "U$1") (pin "DAC0") (pinfunction "DAC0_DAC0") (pintype "bidirectional"))
    )
    (net (code "146") (name "unconnected-(U$1-PadDAC1)") (class "Default")
      (node (ref "U$1") (pin "DAC1") (pinfunction "DAC1_DAC1") (pintype "bidirectional"))
    )
    (net (code "147") (name "unconnected-(U$1-PadGND1)") (class "Default")
      (node (ref "U$1") (pin "GND1") (pinfunction "GND1_GND1") (pintype "bidirectional"))
    )
    (net (code "148") (name "unconnected-(U$1-PadIOREF)") (class "Default")
      (node (ref "U$1") (pin "IOREF") (pinfunction "IOREF_IOREF") (pintype "bidirectional"))
    )
    (net (code "149") (name "unconnected-(U$1-PadNC)") (class "Default")
      (node (ref "U$1") (pin "NC") (pinfunction "NC_NC") (pintype "bidirectional"))
    )
    (net (code "150") (name "unconnected-(U$1-PadRESET)") (class "Default")
      (node (ref "U$1") (pin "RESET") (pinfunction "RESET_RESET") (pintype "bidirectional"))
    )
    (net (code "151") (name "unconnected-(U$1-PadRX0)") (class "Default")
      (node (ref "U$1") (pin "RX0") (pinfunction "RX0_RX0") (pintype "bidirectional"))
    )
    (net (code "152") (name "unconnected-(U$1-PadRX1)") (class "Default")
      (node (ref "U$1") (pin "RX1") (pinfunction "RX1_RX1") (pintype "bidirectional"))
    )
    (net (code "153") (name "unconnected-(U$1-PadRX2)") (class "Default")
      (node (ref "U$1") (pin "RX2") (pinfunction "RX2_RX2") (pintype "bidirectional"))
    )
    (net (code "154") (name "unconnected-(U$1-PadRX3)") (class "Default")
      (node (ref "U$1") (pin "RX3") (pinfunction "RX3_RX3") (pintype "bidirectional"))
    )
    (net (code "155") (name "unconnected-(U$1-PadSCL)") (class "Default")
      (node (ref "U$1") (pin "SCL") (pinfunction "SCL_SCL") (pintype "bidirectional"))
    )
    (net (code "156") (name "unconnected-(U$1-PadSCL1)") (class "Default")
      (node (ref "U$1") (pin "SCL1") (pinfunction "SCL1_SCL1") (pintype "bidirectional"))
    )
    (net (code "157") (name "unconnected-(U$1-PadSDA)") (class "Default")
      (node (ref "U$1") (pin "SDA") (pinfunction "SDA_SDA") (pintype "bidirectional"))
    )
    (net (code "158") (name "unconnected-(U$1-PadSDA1)") (class "Default")
      (node (ref "U$1") (pin "SDA1") (pinfunction "SDA1_SDA1") (pintype "bidirectional"))
    )
    (net (code "159") (name "unconnected-(U$1-PadTX0)") (class "Default")
      (node (ref "U$1") (pin "TX0") (pinfunction "TX0_TX0") (pintype "bidirectional"))
    )
    (net (code "160") (name "unconnected-(U$1-PadTX1)") (class "Default")
      (node (ref "U$1") (pin "TX1") (pinfunction "TX1_TX1") (pintype "bidirectional"))
    )
    (net (code "161") (name "unconnected-(U$1-PadTX2)") (class "Default")
      (node (ref "U$1") (pin "TX2") (pinfunction "TX2_TX2") (pintype "bidirectional"))
    )
    (net (code "162") (name "unconnected-(U$1-PadTX3)") (class "Default")
      (node (ref "U$1") (pin "TX3") (pinfunction "TX3_TX3") (pintype "bidirectional"))
    )
    (net (code "163") (name "unconnected-(U$1-PadVIN)") (class "Default")
      (node (ref "U$1") (pin "VIN") (pinfunction "VIN_VIN") (pintype "bidirectional"))
    )
  )
)
